# MRCS-RING_GENERATOR-BREAKOUT.net
KiCad netlist of a schematic drawn in EAGLE
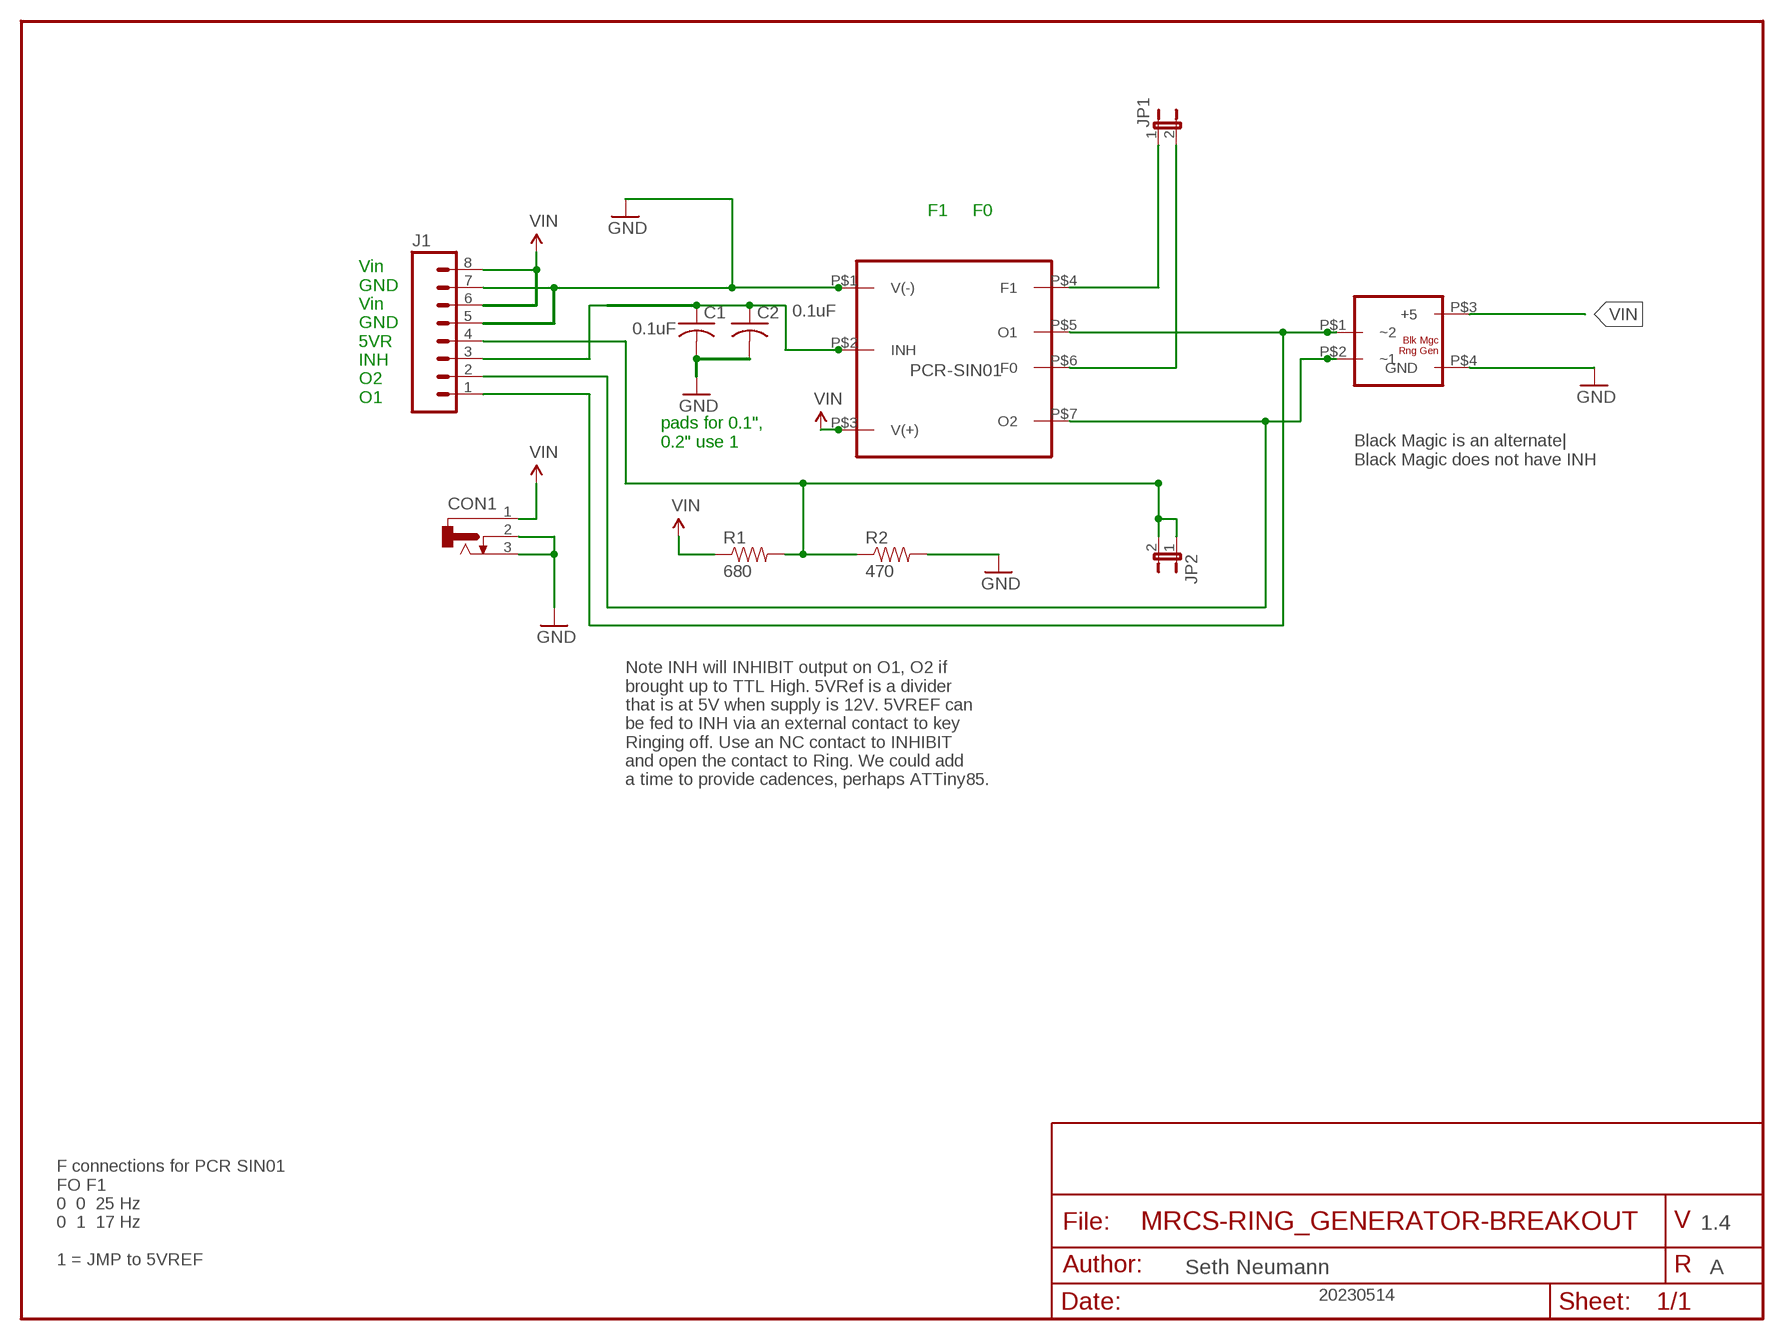
[diagram p0: schematic, sheet 1]

(export (version "E")
  (design (tool "Eeschema 10.0.6"))
  (components
    (comp (ref "C1")
      (value "0.1uF")
      (footprint "eagle-import:C050-024X044")
      (libsource (lib "eagle-import") (part "CAPPTH1"))
    )
    (comp (ref "C2")
      (value "0.1uF")
      (footprint "eagle-import:C-PTH-0.100")
      (libsource (lib "eagle-import") (part "CAPPTH2"))
    )
    (comp (ref "CON1")
      (value "CONNECTOR-DC-POWER-RA")
      (footprint "eagle-import:DCJ0202")
      (libsource (lib "eagle-import") (part "CONNECTOR-DC-POWER-RA"))
    )
    (comp (ref "J1")
      (value "CONNECTOR-M08LOCK")
      (footprint "eagle-import:1X08_LOCK")
      (libsource (lib "eagle-import") (part "CONNECTOR-M08LOCK"))
    )
    (comp (ref "JP1")
      (value "JUMPER-2PTH_LOCK")
      (footprint "eagle-import:1X02_LOCK")
      (libsource (lib "eagle-import") (part "JUMPER-2PTH_LOCK"))
    )
    (comp (ref "JP2")
      (value "JUMPER-2PTH_LOCK")
      (footprint "eagle-import:1X02_LOCK")
      (libsource (lib "eagle-import") (part "JUMPER-2PTH_LOCK"))
    )
    (comp (ref "R1")
      (value "680")
      (footprint "eagle-import:AXIAL-0.4-RES")
      (libsource (lib "eagle-import") (part "RPTH04"))
    )
    (comp (ref "R2")
      (value "470")
      (footprint "eagle-import:AXIAL-0.4-RES")
      (libsource (lib "eagle-import") (part "RPTH04"))
    )
    (comp (ref "U$1")
      (value "PCR-SIN01")
      (footprint "eagle-import:PCR-SIN01")
      (libsource (lib "eagle-import") (part "PCR-SIN01"))
    )
    (comp (ref "U$5")
      (value "BLACK_MAGIC_RING_GEN")
      (footprint "eagle-import:BLACK_MAGIC_RING_GEN")
      (libsource (lib "eagle-import") (part "BLACK_MAGIC_RING_GEN"))
    )
  )
  (nets
    (net (code "1") (name "GND") (class "Default")
      (node (ref "C1") (pin "2") (pinfunction "2_2") (pintype "passive"))
      (node (ref "C2") (pin "2") (pinfunction "2_2") (pintype "passive"))
      (node (ref "CON1") (pin "2") (pinfunction "2_2") (pintype "passive"))
      (node (ref "CON1") (pin "3") (pinfunction "3_3") (pintype "passive"))
      (node (ref "J1") (pin "5") (pinfunction "5_5") (pintype "passive"))
      (node (ref "J1") (pin "7") (pinfunction "7_7") (pintype "passive"))
      (node (ref "R2") (pin "P$2") (pinfunction "2_P$2") (pintype "passive"))
      (node (ref "U$1") (pin "P$1") (pinfunction "V(-)_P$1") (pintype "bidirectional"))
      (node (ref "U$5") (pin "P$4") (pinfunction "GND_P$4") (pintype "bidirectional"))
    )
    (net (code "2") (name "Net-(R1-2)") (class "Default")
      (node (ref "J1") (pin "4") (pinfunction "4_4") (pintype "passive"))
      (node (ref "JP2") (pin "1") (pinfunction "1_1") (pintype "passive"))
      (node (ref "JP2") (pin "2") (pinfunction "2_2") (pintype "passive"))
      (node (ref "R1") (pin "P$2") (pinfunction "2_P$2") (pintype "passive"))
      (node (ref "R2") (pin "P$1") (pinfunction "1_P$1") (pintype "passive"))
    )
    (net (code "3") (name "Net-(U$1-F0)") (class "Default")
      (node (ref "JP1") (pin "2") (pinfunction "2_2") (pintype "passive"))
      (node (ref "U$1") (pin "P$6") (pinfunction "F0_P$6") (pintype "bidirectional"))
    )
    (net (code "4") (name "Net-(U$1-F1)") (class "Default")
      (node (ref "JP1") (pin "1") (pinfunction "1_1") (pintype "passive"))
      (node (ref "U$1") (pin "P$4") (pinfunction "F1_P$4") (pintype "bidirectional"))
    )
    (net (code "5") (name "Net-(U$1-INH)") (class "Default")
      (node (ref "C1") (pin "1") (pinfunction "1_1") (pintype "passive"))
      (node (ref "C2") (pin "1") (pinfunction "1_1") (pintype "passive"))
      (node (ref "J1") (pin "3") (pinfunction "3_3") (pintype "passive"))
      (node (ref "U$1") (pin "P$2") (pinfunction "INH_P$2") (pintype "bidirectional"))
    )
    (net (code "6") (name "Net-(U$1-O1)") (class "Default")
      (node (ref "J1") (pin "1") (pinfunction "1_1") (pintype "passive"))
      (node (ref "U$1") (pin "P$5") (pinfunction "O1_P$5") (pintype "bidirectional"))
      (node (ref "U$5") (pin "P$1") (pinfunction "~{2}_P$1") (pintype "bidirectional"))
    )
    (net (code "7") (name "Net-(U$1-O2)") (class "Default")
      (node (ref "J1") (pin "2") (pinfunction "2_2") (pintype "passive"))
      (node (ref "U$1") (pin "P$7") (pinfunction "O2_P$7") (pintype "bidirectional"))
      (node (ref "U$5") (pin "P$2") (pinfunction "~{1}_P$2") (pintype "bidirectional"))
    )
    (net (code "8") (name "VIN") (class "Default")
      (node (ref "CON1") (pin "1") (pinfunction "1_1") (pintype "passive"))
      (node (ref "J1") (pin "6") (pinfunction "6_6") (pintype "passive"))
      (node (ref "J1") (pin "8") (pinfunction "8_8") (pintype "passive"))
      (node (ref "R1") (pin "P$1") (pinfunction "1_P$1") (pintype "passive"))
      (node (ref "U$1") (pin "P$3") (pinfunction "V(+)_P$3") (pintype "bidirectional"))
      (node (ref "U$5") (pin "P$3") (pinfunction "+5_P$3") (pintype "bidirectional"))
    )
  )
)
